# Memoria.net
KiCad netlist of a schematic drawn in Altium Designer
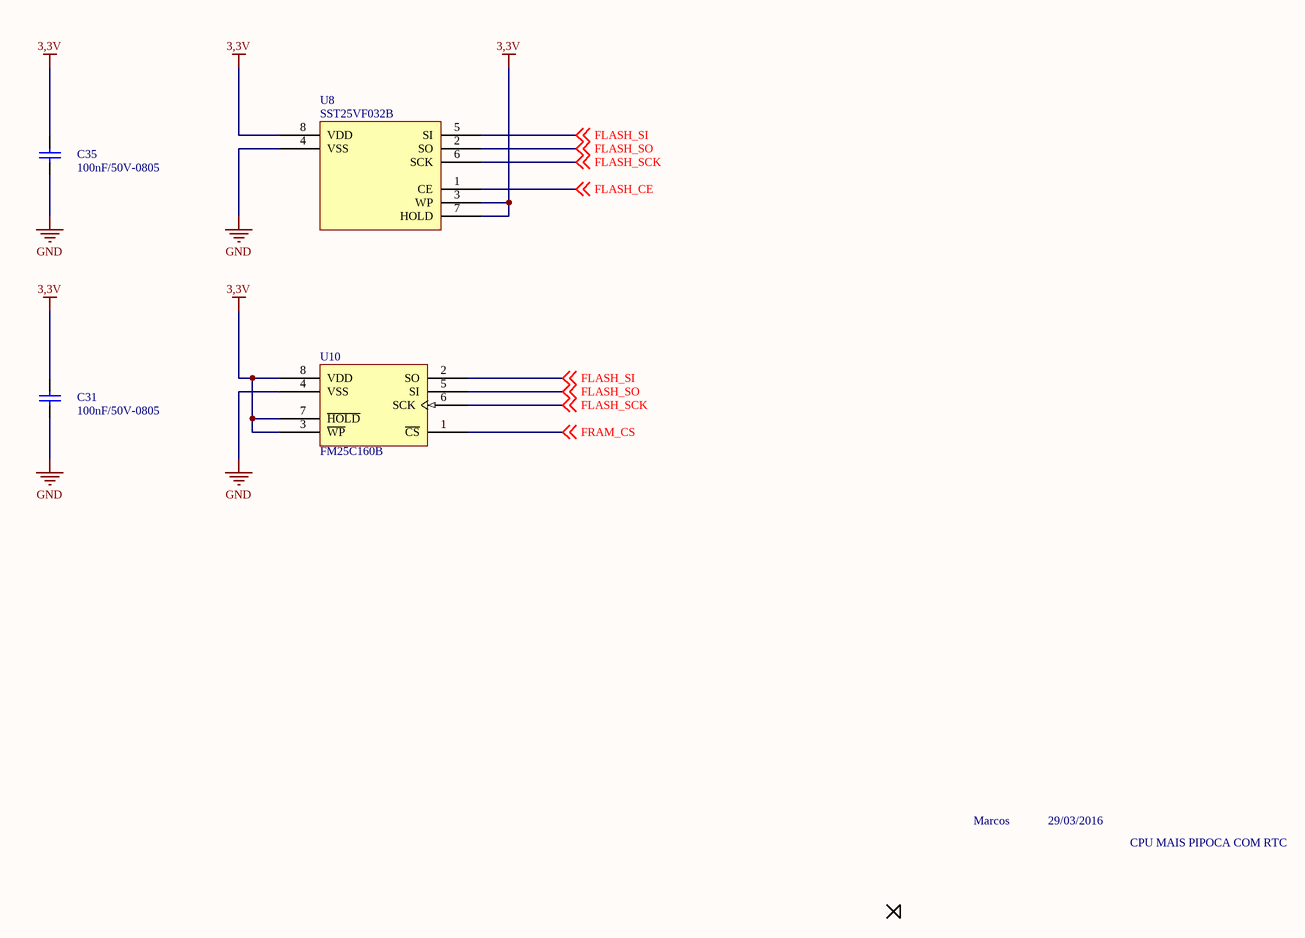
[diagram p0: Memoria.SchDoc]

(export (version "E")
  (design (tool "Eeschema 10.0.6"))
  (components
    (comp (ref "C31")
      (value "100nF/50V-0805")
      (footprint "0805-REVISADO O")
      (description "100nF/50-0805-NPO")
      (libsource (lib "AquinoLib") (part "100nF/50-0805-NPO"))
    )
    (comp (ref "C35")
      (value "100nF/50V-0805")
      (footprint "0805-REVISADO O")
      (description "100nF/50-0805-NPO")
      (libsource (lib "AquinoLib") (part "100nF/50-0805-NPO"))
    )
    (comp (ref "U8")
      (value "SST25VF032B")
      (footprint "SOIC LARGO ATME")
      (libsource (lib "ChaveDigital3") (part "SST25VF032B"))
    )
    (comp (ref "U10")
      (value "FM25C160B")
      (footprint "SOIC-08")
      (libsource (lib "AquinoLib") (part "FM25C160B"))
    )
  )
  (nets
    (net (code "1") (name "3,3V") (class "Default")
      (node (ref "C31") (pin "2") (pinfunction "2_2") (pintype "passive"))
      (node (ref "C35") (pin "2") (pinfunction "2_2") (pintype "passive"))
      (node (ref "U10") (pin "3") (pinfunction "~{WP}_3") (pintype "passive"))
      (node (ref "U10") (pin "7") (pinfunction "~{HOLD}_7") (pintype "passive"))
      (node (ref "U10") (pin "8") (pinfunction "VDD_8") (pintype "passive"))
      (node (ref "U8") (pin "3") (pinfunction "WP_3") (pintype "passive"))
      (node (ref "U8") (pin "7") (pinfunction "HOLD_7") (pintype "passive"))
      (node (ref "U8") (pin "8") (pinfunction "VDD_8") (pintype "passive"))
    )
    (net (code "2") (name "FLASH_CE") (class "Default")
      (node (ref "U8") (pin "1") (pinfunction "CE_1") (pintype "passive"))
    )
    (net (code "3") (name "FLASH_SCK") (class "Default")
      (node (ref "U10") (pin "6") (pinfunction "SCK_6") (pintype "input"))
      (node (ref "U8") (pin "6") (pinfunction "SCK_6") (pintype "passive"))
    )
    (net (code "4") (name "FLASH_SI") (class "Default")
      (node (ref "U10") (pin "2") (pinfunction "SO_2") (pintype "passive"))
      (node (ref "U8") (pin "5") (pinfunction "SI_5") (pintype "passive"))
    )
    (net (code "5") (name "FLASH_SO") (class "Default")
      (node (ref "U10") (pin "5") (pinfunction "SI_5") (pintype "passive"))
      (node (ref "U8") (pin "2") (pinfunction "SO_2") (pintype "passive"))
    )
    (net (code "6") (name "FRAM_CS") (class "Default")
      (node (ref "U10") (pin "1") (pinfunction "~{CS}_1") (pintype "passive"))
    )
    (net (code "7") (name "GND") (class "Default")
      (node (ref "C31") (pin "1") (pinfunction "1_1") (pintype "passive"))
      (node (ref "C35") (pin "1") (pinfunction "1_1") (pintype "passive"))
      (node (ref "U10") (pin "4") (pinfunction "VSS_4") (pintype "passive"))
      (node (ref "U8") (pin "4") (pinfunction "VSS_4") (pintype "passive"))
    )
  )
)
